# RPI_schematics.net
KiCad netlist of a schematic drawn in Altium Designer
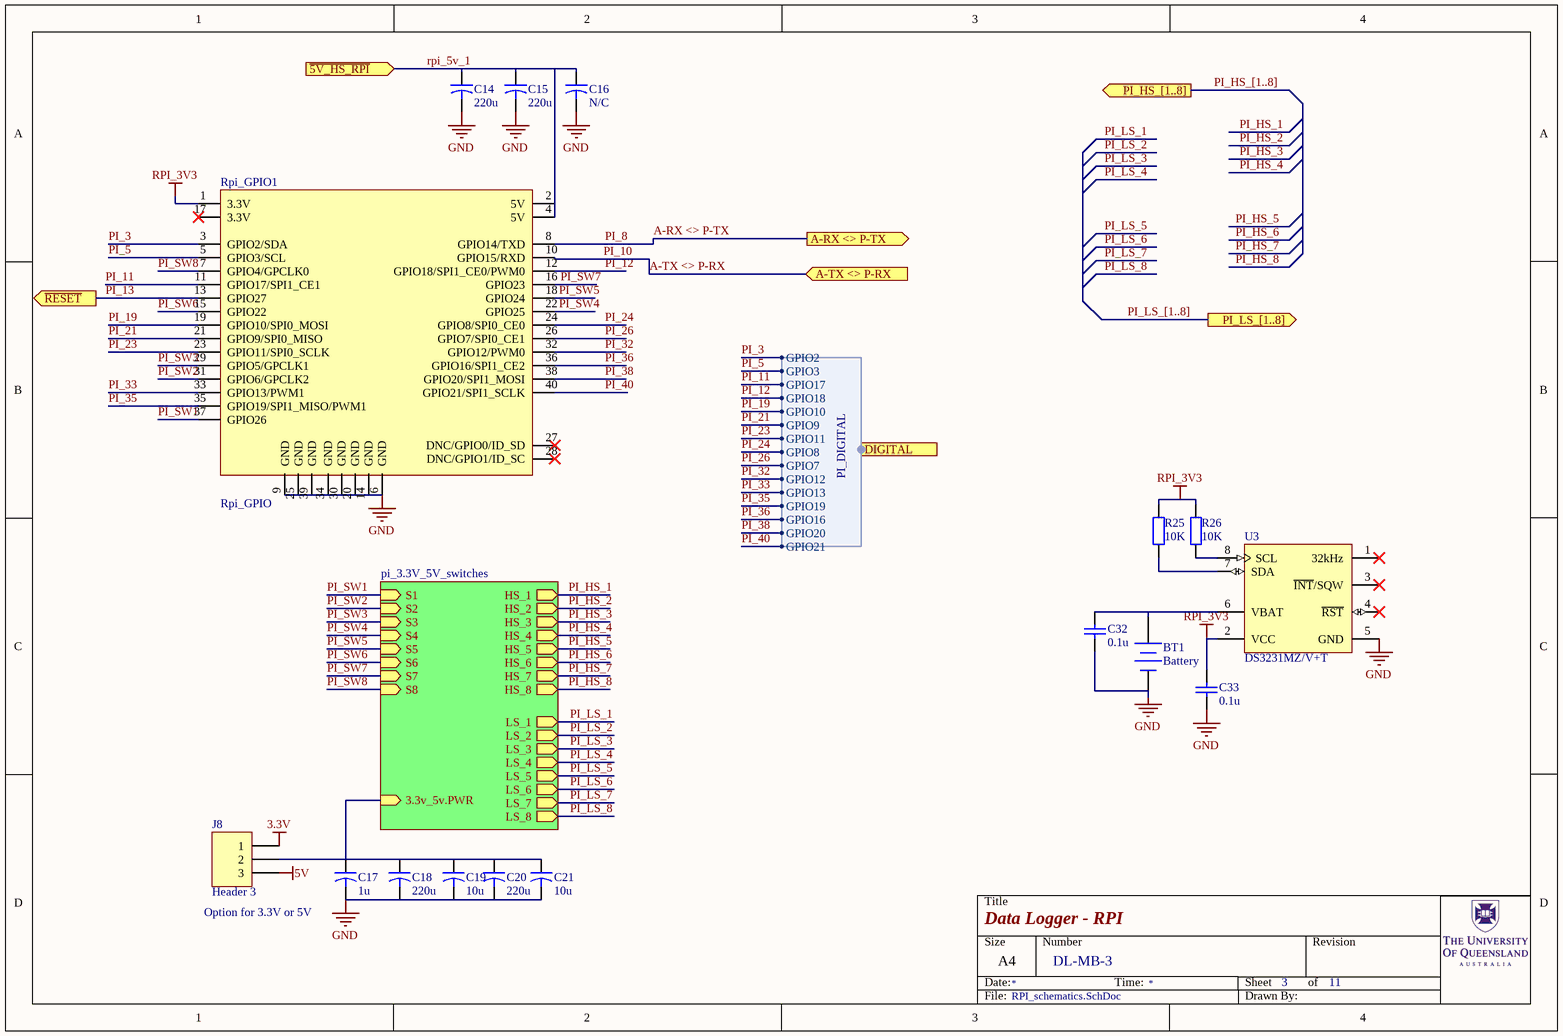
[diagram p0: RPI_schematics.SchDoc]

(export (version "E")
  (design (tool "Eeschema 10.0.6"))
  (components
    (comp (ref "BT1")
      (value "Battery")
      (footprint "COIN-2032")
      (description "Multicell Battery")
      (libsource (lib "Miscellaneous Devices") (part "Battery"))
    )
    (comp (ref "C14")
      (value "220u")
      (footprint "CAPR5-4X5")
      (description "Capacitor")
      (fields (field (name "PUBLISHER") "Altium Limited"))
      (libsource (lib "Datalogger") (part "Cap Pol1"))
    )
    (comp (ref "C15")
      (value "220u")
      (footprint "CAPAE9083X80M")
      (description "Capacitor")
      (fields (field (name "PUBLISHER") "Altium Limited"))
      (libsource (lib "Datalogger") (part "Cap Pol1"))
    )
    (comp (ref "C16")
      (value "N/C")
      (footprint "CAPR5-4X5")
      (description "Capacitor")
      (fields (field (name "PUBLISHER") "Altium Limited"))
      (libsource (lib "Datalogger") (part "Cap Pol1"))
    )
    (comp (ref "C17")
      (value "1u")
      (footprint "CAPR5-4X5")
      (description "Capacitor")
      (fields (field (name "PUBLISHER") "Altium Limited"))
      (libsource (lib "Datalogger") (part "Cap Pol1"))
    )
    (comp (ref "C18")
      (value "220u")
      (footprint "CAPAE9083X80M")
      (description "Capacitor")
      (fields (field (name "PUBLISHER") "Altium Limited"))
      (libsource (lib "Datalogger") (part "Cap Pol1"))
    )
    (comp (ref "C19")
      (value "10u")
      (footprint "CAPR5-4X5")
      (description "Capacitor")
      (fields (field (name "PUBLISHER") "Altium Limited"))
      (libsource (lib "Datalogger") (part "Cap Pol1"))
    )
    (comp (ref "C20")
      (value "220u")
      (footprint "CAPR5-4X5")
      (description "Capacitor")
      (fields (field (name "PUBLISHER") "Altium Limited"))
      (libsource (lib "Datalogger") (part "Cap Pol1"))
    )
    (comp (ref "C21")
      (value "10u")
      (footprint "CAPR5-4X5")
      (description "Capacitor")
      (fields (field (name "PUBLISHER") "Altium Limited"))
      (libsource (lib "Datalogger") (part "Cap Pol1"))
    )
    (comp (ref "C32")
      (value "0.1u")
      (footprint "RES-1206_M")
      (description "Capacitor (Semiconductor SIM Model)")
      (fields (field (name "PUBLISHER") "Altium Limited"))
      (libsource (lib "Datalogger") (part "Cap Semi"))
    )
    (comp (ref "C33")
      (value "0.1u")
      (footprint "RES-1206_M")
      (description "Capacitor (Semiconductor SIM Model)")
      (fields (field (name "PUBLISHER") "Altium Limited"))
      (libsource (lib "Datalogger") (part "Cap Semi"))
    )
    (comp (ref "J8")
      (value "Header 3")
      (footprint "HDR1X3")
      (description "Header, 3-Pin\r\nRPI, 5V or 3V Power")
      (fields (field (name "PUBLISHER") "Altium Limited"))
      (libsource (lib "Miscellaneous Connectors") (part "Header 3"))
    )
    (comp (ref "R25")
      (value "10K")
      (footprint "RES-1206_M")
      (description "Resistor")
      (fields (field (name "PUBLISHER") "Altium Limited"))
      (libsource (lib "Datalogger") (part "Res2"))
    )
    (comp (ref "R26")
      (value "10K")
      (footprint "RES-1206_M")
      (description "Resistor")
      (fields (field (name "PUBLISHER") "Altium Limited"))
      (libsource (lib "Datalogger") (part "Res2"))
    )
    (comp (ref "Rpi_GPIO1")
      (value "Rpi_GPIO")
      (footprint "RPI_Z_GPIO_HDR2X20")
      (description "Header, 20-Pin, Dual row")
      (fields (field (name "PUBLISHER") "Altium Limited"))
      (libsource (lib "Datalogger") (part "Rpi_GPIO_1"))
    )
    (comp (ref "U3")
      (value "DS3231MZ/V+T")
      (footprint "S8MK+1_N")
      (libsource (lib "Altium Content Vault") (part "MAX-RTC-8-DS3231MZ-S8MK+1"))
    )
  )
  (nets
    (net (code "2") (name "/3.3v_5v.PWR") (class "Default")
      (node (ref "C17") (pin "1") (pinfunction "1_1") (pintype "passive"))
      (node (ref "C18") (pin "1") (pinfunction "1_1") (pintype "passive"))
      (node (ref "C19") (pin "1") (pinfunction "1_1") (pintype "passive"))
      (node (ref "C20") (pin "1") (pinfunction "1_1") (pintype "passive"))
      (node (ref "C21") (pin "1") (pinfunction "1_1") (pintype "passive"))
      (node (ref "J8") (pin "2") (pinfunction "2_2") (pintype "passive"))
    )
    (net (code "3") (name "/A-RX <> P-TX") (class "Default")
      (node (ref "Rpi_GPIO1") (pin "8") (pinfunction "GPIO14/TXD_8") (pintype "passive"))
    )
    (net (code "4") (name "/A-TX <> P-RX") (class "Default")
      (node (ref "Rpi_GPIO1") (pin "10") (pinfunction "GPIO15/RXD_10") (pintype "passive"))
    )
    (net (code "5") (name "/PI_3") (class "Default")
      (node (ref "Rpi_GPIO1") (pin "3") (pinfunction "GPIO2/SDA_3") (pintype "passive"))
    )
    (net (code "6") (name "/PI_5") (class "Default")
      (node (ref "Rpi_GPIO1") (pin "5") (pinfunction "GPIO3/SCL_5") (pintype "passive"))
    )
    (net (code "7") (name "/PI_11") (class "Default")
      (node (ref "Rpi_GPIO1") (pin "11") (pinfunction "GPIO17/SPI1_CE1_11") (pintype "passive"))
    )
    (net (code "8") (name "/PI_12") (class "Default")
      (node (ref "Rpi_GPIO1") (pin "12") (pinfunction "GPIO18/SPI1_CE0/PWM0_12") (pintype "passive"))
    )
    (net (code "9") (name "/PI_13") (class "Default")
      (node (ref "Rpi_GPIO1") (pin "13") (pinfunction "GPIO27_13") (pintype "passive"))
    )
    (net (code "10") (name "/PI_19") (class "Default")
      (node (ref "Rpi_GPIO1") (pin "19") (pinfunction "GPIO10/SPI0_MOSI_19") (pintype "passive"))
    )
    (net (code "11") (name "/PI_21") (class "Default")
      (node (ref "Rpi_GPIO1") (pin "21") (pinfunction "GPIO9/SPI0_MISO_21") (pintype "passive"))
    )
    (net (code "12") (name "/PI_23") (class "Default")
      (node (ref "Rpi_GPIO1") (pin "23") (pinfunction "GPIO11/SPI0_SCLK_23") (pintype "passive"))
    )
    (net (code "13") (name "/PI_24") (class "Default")
      (node (ref "Rpi_GPIO1") (pin "24") (pinfunction "GPIO8/SPI0_CE0_24") (pintype "passive"))
    )
    (net (code "14") (name "/PI_26") (class "Default")
      (node (ref "Rpi_GPIO1") (pin "26") (pinfunction "GPIO7/SPI0_CE1_26") (pintype "passive"))
    )
    (net (code "15") (name "/PI_32") (class "Default")
      (node (ref "Rpi_GPIO1") (pin "32") (pinfunction "GPIO12/PWM0_32") (pintype "passive"))
    )
    (net (code "16") (name "/PI_33") (class "Default")
      (node (ref "Rpi_GPIO1") (pin "33") (pinfunction "GPIO13/PWM1_33") (pintype "passive"))
    )
    (net (code "17") (name "/PI_35") (class "Default")
      (node (ref "Rpi_GPIO1") (pin "35") (pinfunction "GPIO19/SPI1_MISO/PWM1_35") (pintype "passive"))
    )
    (net (code "18") (name "/PI_36") (class "Default")
      (node (ref "Rpi_GPIO1") (pin "36") (pinfunction "GPIO16/SPI1_CE2_36") (pintype "passive"))
    )
    (net (code "19") (name "/PI_38") (class "Default")
      (node (ref "Rpi_GPIO1") (pin "38") (pinfunction "GPIO20/SPI1_MOSI_38") (pintype "passive"))
    )
    (net (code "20") (name "/PI_40") (class "Default")
      (node (ref "Rpi_GPIO1") (pin "40") (pinfunction "GPIO21/SPI1_SCLK_40") (pintype "passive"))
    )
    (net (code "39") (name "/PI_SW1") (class "Default")
      (node (ref "Rpi_GPIO1") (pin "37") (pinfunction "GPIO26_37") (pintype "passive"))
    )
    (net (code "40") (name "/PI_SW2") (class "Default")
      (node (ref "Rpi_GPIO1") (pin "31") (pinfunction "GPIO6/GPCLK2_31") (pintype "passive"))
    )
    (net (code "41") (name "/PI_SW3") (class "Default")
      (node (ref "Rpi_GPIO1") (pin "29") (pinfunction "GPIO5/GPCLK1_29") (pintype "passive"))
    )
    (net (code "42") (name "/PI_SW4") (class "Default")
      (node (ref "Rpi_GPIO1") (pin "22") (pinfunction "GPIO25_22") (pintype "passive"))
    )
    (net (code "43") (name "/PI_SW5") (class "Default")
      (node (ref "Rpi_GPIO1") (pin "18") (pinfunction "GPIO24_18") (pintype "passive"))
    )
    (net (code "44") (name "/PI_SW6") (class "Default")
      (node (ref "Rpi_GPIO1") (pin "15") (pinfunction "GPIO22_15") (pintype "passive"))
    )
    (net (code "45") (name "/PI_SW7") (class "Default")
      (node (ref "Rpi_GPIO1") (pin "16") (pinfunction "GPIO23_16") (pintype "passive"))
    )
    (net (code "46") (name "/PI_SW8") (class "Default")
      (node (ref "Rpi_GPIO1") (pin "7") (pinfunction "GPIO4/GPCLK0_7") (pintype "passive"))
    )
    (net (code "47") (name "/rpi_5v_1") (class "Default")
      (node (ref "C14") (pin "1") (pinfunction "1_1") (pintype "passive"))
      (node (ref "C15") (pin "1") (pinfunction "1_1") (pintype "passive"))
      (node (ref "C16") (pin "1") (pinfunction "1_1") (pintype "passive"))
      (node (ref "Rpi_GPIO1") (pin "2") (pinfunction "5V_2") (pintype "passive"))
      (node (ref "Rpi_GPIO1") (pin "4") (pinfunction "5V_4") (pintype "passive"))
    )
    (net (code "49") (name "3.3V") (class "Default")
      (node (ref "J8") (pin "1") (pinfunction "1_1") (pintype "passive"))
    )
    (net (code "50") (name "5V") (class "Default")
      (node (ref "J8") (pin "3") (pinfunction "3_3") (pintype "passive"))
    )
    (net (code "51") (name "GND") (class "Default")
      (node (ref "BT1") (pin "2") (pinfunction "-_2") (pintype "passive"))
      (node (ref "C14") (pin "2") (pinfunction "2_2") (pintype "passive"))
      (node (ref "C15") (pin "2") (pinfunction "2_2") (pintype "passive"))
      (node (ref "C16") (pin "2") (pinfunction "2_2") (pintype "passive"))
      (node (ref "C17") (pin "2") (pinfunction "2_2") (pintype "passive"))
      (node (ref "C18") (pin "2") (pinfunction "2_2") (pintype "passive"))
      (node (ref "C19") (pin "2") (pinfunction "2_2") (pintype "passive"))
      (node (ref "C20") (pin "2") (pinfunction "2_2") (pintype "passive"))
      (node (ref "C21") (pin "2") (pinfunction "2_2") (pintype "passive"))
      (node (ref "C32") (pin "2") (pinfunction "2_2") (pintype "passive"))
      (node (ref "C33") (pin "2") (pinfunction "2_2") (pintype "passive"))
      (node (ref "Rpi_GPIO1") (pin "14") (pinfunction "GND_14") (pintype "passive"))
      (node (ref "Rpi_GPIO1") (pin "20") (pinfunction "GND_20") (pintype "passive"))
      (node (ref "Rpi_GPIO1") (pin "25") (pinfunction "GND_25") (pintype "passive"))
      (node (ref "Rpi_GPIO1") (pin "30") (pinfunction "GND_30") (pintype "passive"))
      (node (ref "Rpi_GPIO1") (pin "34") (pinfunction "GND_34") (pintype "passive"))
      (node (ref "Rpi_GPIO1") (pin "39") (pinfunction "GND_39") (pintype "passive"))
      (node (ref "Rpi_GPIO1") (pin "6") (pinfunction "GND_6") (pintype "passive"))
      (node (ref "Rpi_GPIO1") (pin "9") (pinfunction "GND_9") (pintype "passive"))
      (node (ref "U3") (pin "5") (pinfunction "GND_5") (pintype "power_in"))
    )
    (net (code "52") (name "Net-(BT1-+)") (class "Default")
      (node (ref "BT1") (pin "1") (pinfunction "+_1") (pintype "passive"))
      (node (ref "C32") (pin "1") (pinfunction "1_1") (pintype "passive"))
      (node (ref "U3") (pin "6") (pinfunction "VBAT_6") (pintype "power_in"))
    )
    (net (code "53") (name "Net-(U3-SCL)") (class "Default")
      (node (ref "R26") (pin "2") (pinfunction "2_2") (pintype "passive"))
      (node (ref "U3") (pin "8") (pinfunction "SCL_8") (pintype "input"))
    )
    (net (code "54") (name "Net-(U3-SDA)") (class "Default")
      (node (ref "R25") (pin "2") (pinfunction "2_2") (pintype "passive"))
      (node (ref "U3") (pin "7") (pinfunction "SDA_7") (pintype "bidirectional"))
    )
    (net (code "55") (name "RPI_3V3") (class "Default")
      (node (ref "C33") (pin "1") (pinfunction "1_1") (pintype "passive"))
      (node (ref "R25") (pin "1") (pinfunction "1_1") (pintype "passive"))
      (node (ref "R26") (pin "1") (pinfunction "1_1") (pintype "passive"))
      (node (ref "Rpi_GPIO1") (pin "1") (pinfunction "3.3V_1") (pintype "passive"))
      (node (ref "U3") (pin "2") (pinfunction "VCC_2") (pintype "power_in"))
    )
    (net (code "56") (name "unconnected-(Rpi_GPIO1-3.3V-Pad17)") (class "Default")
      (node (ref "Rpi_GPIO1") (pin "17") (pinfunction "3.3V_17") (pintype "passive+no_connect"))
    )
    (net (code "57") (name "unconnected-(Rpi_GPIO1-DNC{slash}GPIO0{slash}ID_SD-Pad27)") (class "Default")
      (node (ref "Rpi_GPIO1") (pin "27") (pinfunction "DNC/GPIO0/ID_SD_27") (pintype "passive+no_connect"))
    )
    (net (code "58") (name "unconnected-(Rpi_GPIO1-DNC{slash}GPIO1{slash}ID_SC-Pad28)") (class "Default")
      (node (ref "Rpi_GPIO1") (pin "28") (pinfunction "DNC/GPIO1/ID_SC_28") (pintype "passive+no_connect"))
    )
    (net (code "59") (name "unconnected-(U3-32kHz-Pad1)") (class "Default")
      (node (ref "U3") (pin "1") (pinfunction "32kHz_1") (pintype "open_collector+no_connect"))
    )
    (net (code "60") (name "unconnected-(U3-~{INT}{slash}SQW-Pad3)") (class "Default")
      (node (ref "U3") (pin "3") (pinfunction "~{INT}/SQW_3") (pintype "open_collector+no_connect"))
    )
    (net (code "61") (name "unconnected-(U3-~{RST}-Pad4)") (class "Default")
      (node (ref "U3") (pin "4") (pinfunction "~{RST}_4") (pintype "bidirectional+no_connect"))
    )
  )
)
